# SlimPow-CB-v2.net
KiCad netlist of a schematic drawn in EAGLE
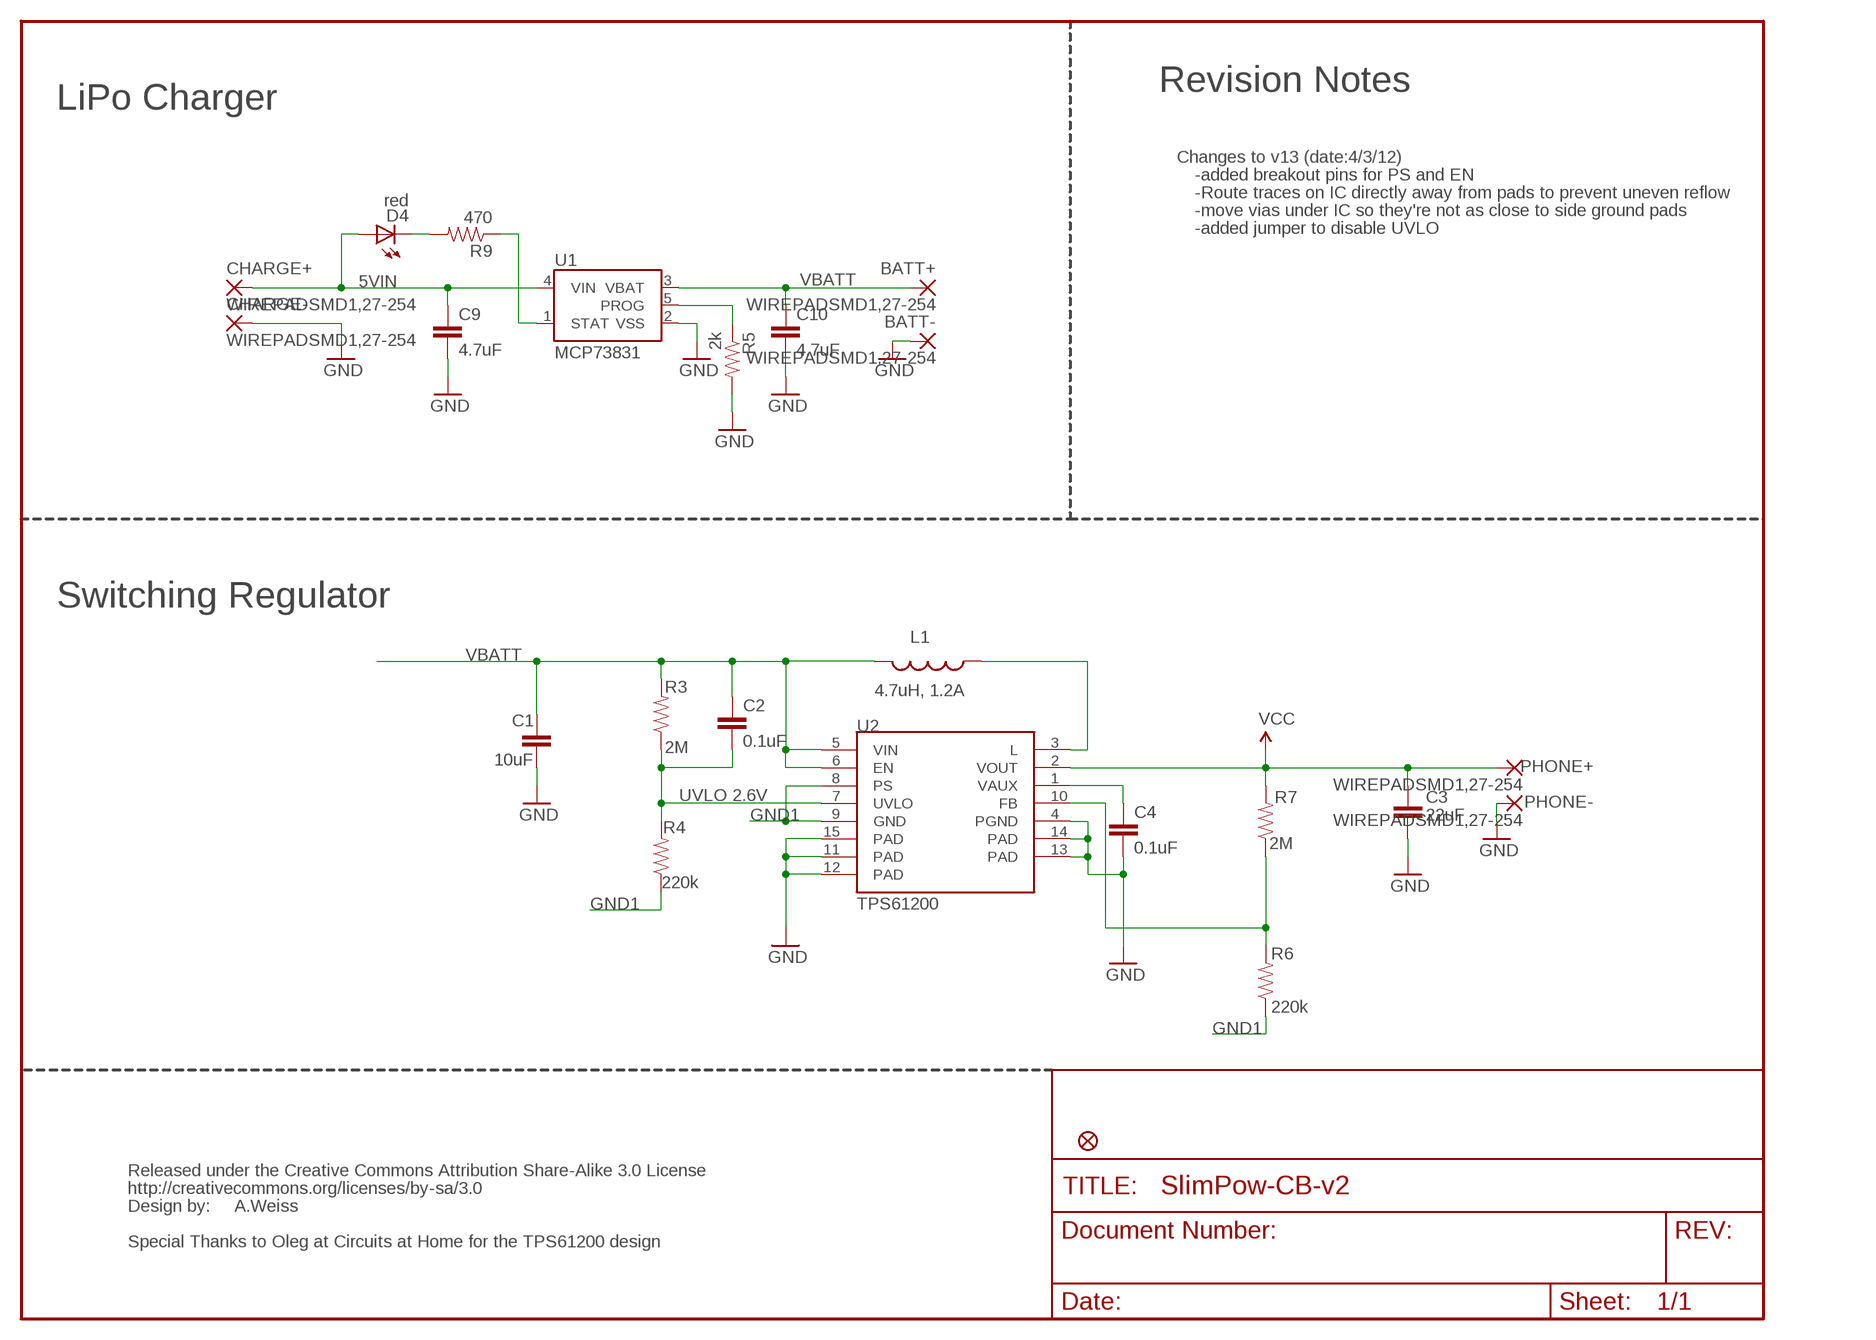
[diagram p0: schematic, sheet 1]

(export (version "E")
  (design (tool "Eeschema 10.0.6"))
  (components
    (comp (ref "BATT+")
      (value "WIREPADSMD1,27-254")
      (footprint "eagle-import:SMD1,27-2,54")
      (libsource (lib "eagle-import") (part "WIREPADSMD1,27-254"))
    )
    (comp (ref "BATT-")
      (value "WIREPADSMD1,27-254")
      (footprint "eagle-import:SMD1,27-2,54")
      (libsource (lib "eagle-import") (part "WIREPADSMD1,27-254"))
    )
    (comp (ref "C1")
      (value "10uF")
      (footprint "eagle-import:1206")
      (libsource (lib "eagle-import") (part "CAP1206"))
    )
    (comp (ref "C2")
      (value "0.1uF")
      (footprint "eagle-import:0402-CAP")
      (libsource (lib "eagle-import") (part "CAP0402-CAP"))
    )
    (comp (ref "C3")
      (value "22uF")
      (footprint "eagle-import:0805")
      (libsource (lib "eagle-import") (part "CAP0805"))
    )
    (comp (ref "C4")
      (value "0.1uF")
      (footprint "eagle-import:0402-CAP")
      (libsource (lib "eagle-import") (part "CAP0402-CAP"))
    )
    (comp (ref "C9")
      (value "4.7uF")
      (footprint "eagle-import:0402-CAP")
      (libsource (lib "eagle-import") (part "CAP0402-CAP"))
    )
    (comp (ref "C10")
      (value "4.7uF")
      (footprint "eagle-import:0402-CAP")
      (libsource (lib "eagle-import") (part "CAP0402-CAP"))
    )
    (comp (ref "CHARGE+")
      (value "WIREPADSMD1,27-254")
      (footprint "eagle-import:SMD1,27-2,54")
      (libsource (lib "eagle-import") (part "WIREPADSMD1,27-254"))
    )
    (comp (ref "CHARGE-")
      (value "WIREPADSMD1,27-254")
      (footprint "eagle-import:SMD1,27-2,54")
      (libsource (lib "eagle-import") (part "WIREPADSMD1,27-254"))
    )
    (comp (ref "D4")
      (value "red")
      (footprint "eagle-import:LED-0603")
      (libsource (lib "eagle-import") (part "LED0603"))
    )
    (comp (ref "JP15")
      (value "FIDUCIALUFIDUCIAL")
      (footprint "eagle-import:MICRO-FIDUCIAL")
      (libsource (lib "eagle-import") (part "FIDUCIALUFIDUCIAL"))
    )
    (comp (ref "L1")
      (value "4.7uH, 1.2A")
      (footprint "eagle-import:CDRH2D09")
      (libsource (lib "eagle-import") (part "INDUCTOR."))
    )
    (comp (ref "PHONE+")
      (value "WIREPADSMD1,27-254")
      (footprint "eagle-import:SMD1,27-2,54")
      (libsource (lib "eagle-import") (part "WIREPADSMD1,27-254"))
    )
    (comp (ref "PHONE-")
      (value "WIREPADSMD1,27-254")
      (footprint "eagle-import:SMD1,27-2,54")
      (libsource (lib "eagle-import") (part "WIREPADSMD1,27-254"))
    )
    (comp (ref "R3")
      (value "2M")
      (footprint "eagle-import:0402-RES")
      (libsource (lib "eagle-import") (part "RESISTOR0402-RES"))
    )
    (comp (ref "R4")
      (value "220k")
      (footprint "eagle-import:0402-RES")
      (libsource (lib "eagle-import") (part "RESISTOR0402-RES"))
    )
    (comp (ref "R5")
      (value "2k")
      (footprint "eagle-import:0402-RES")
      (libsource (lib "eagle-import") (part "RESISTOR0402-RES"))
    )
    (comp (ref "R6")
      (value "220k")
      (footprint "eagle-import:0402-RES")
      (libsource (lib "eagle-import") (part "RESISTOR0402-RES"))
    )
    (comp (ref "R7")
      (value "2M")
      (footprint "eagle-import:0402-RES")
      (libsource (lib "eagle-import") (part "RESISTOR0402-RES"))
    )
    (comp (ref "R9")
      (value "470")
      (footprint "eagle-import:0402-RES")
      (libsource (lib "eagle-import") (part "RESISTOR0402-RES"))
    )
    (comp (ref "U$2")
      (value "CREATIVE_COMMONS")
      (footprint "eagle-import:CREATIVE_COMMONS")
      (libsource (lib "eagle-import") (part "CREATIVE_COMMONS"))
    )
    (comp (ref "U1")
      (value "MCP73831")
      (footprint "eagle-import:SOT23-5")
      (libsource (lib "eagle-import") (part "MCP73831"))
    )
    (comp (ref "U2")
      (value "TPS61200")
      (footprint "eagle-import:QFN-10_PAD")
      (libsource (lib "eagle-import") (part "TPS61200"))
    )
  )
  (nets
    (net (code "1") (name "/5VIN") (class "Default")
      (node (ref "C9") (pin "1") (pinfunction "1_1") (pintype "passive"))
      (node (ref "CHARGE+") (pin "1") (pinfunction "P_1") (pintype "passive"))
      (node (ref "D4") (pin "A") (pinfunction "A_A") (pintype "passive"))
      (node (ref "U1") (pin "4") (pinfunction "VIN_4") (pintype "power_in"))
    )
    (net (code "2") (name "/GND1") (class "Default")
      (node (ref "R4") (pin "1") (pinfunction "1_1") (pintype "passive"))
      (node (ref "R6") (pin "1") (pinfunction "1_1") (pintype "passive"))
      (node (ref "U2") (pin "8") (pinfunction "PS_8") (pintype "input"))
      (node (ref "U2") (pin "9") (pinfunction "GND_9") (pintype "power_in"))
    )
    (net (code "3") (name "/VBATT") (class "Default")
      (node (ref "BATT+") (pin "1") (pinfunction "P_1") (pintype "passive"))
      (node (ref "C1") (pin "1") (pinfunction "1_1") (pintype "passive"))
      (node (ref "C10") (pin "1") (pinfunction "1_1") (pintype "passive"))
      (node (ref "C2") (pin "1") (pinfunction "1_1") (pintype "passive"))
      (node (ref "L1") (pin "P$2") (pinfunction "2_P$2") (pintype "passive"))
      (node (ref "R3") (pin "2") (pinfunction "2_2") (pintype "passive"))
      (node (ref "U1") (pin "3") (pinfunction "VBAT_3") (pintype "power_in"))
      (node (ref "U2") (pin "5") (pinfunction "VIN_5") (pintype "power_in"))
      (node (ref "U2") (pin "6") (pinfunction "EN_6") (pintype "input"))
    )
    (net (code "4") (name "GND") (class "Default")
      (node (ref "BATT-") (pin "1") (pinfunction "P_1") (pintype "passive"))
      (node (ref "C1") (pin "2") (pinfunction "2_2") (pintype "passive"))
      (node (ref "C10") (pin "2") (pinfunction "2_2") (pintype "passive"))
      (node (ref "C3") (pin "2") (pinfunction "2_2") (pintype "passive"))
      (node (ref "C4") (pin "2") (pinfunction "2_2") (pintype "passive"))
      (node (ref "C9") (pin "2") (pinfunction "2_2") (pintype "passive"))
      (node (ref "CHARGE-") (pin "1") (pinfunction "P_1") (pintype "passive"))
      (node (ref "PHONE-") (pin "1") (pinfunction "P_1") (pintype "passive"))
      (node (ref "R5") (pin "2") (pinfunction "2_2") (pintype "passive"))
      (node (ref "U1") (pin "2") (pinfunction "VSS_2") (pintype "power_in"))
      (node (ref "U2") (pin "11") (pinfunction "PAD_11") (pintype "power_in"))
      (node (ref "U2") (pin "12") (pinfunction "PAD_12") (pintype "power_in"))
      (node (ref "U2") (pin "13") (pinfunction "PAD_13") (pintype "power_in"))
      (node (ref "U2") (pin "14") (pinfunction "PAD_14") (pintype "power_in"))
      (node (ref "U2") (pin "15") (pinfunction "PAD_15") (pintype "power_in"))
      (node (ref "U2") (pin "4") (pinfunction "PGND_4") (pintype "power_in"))
    )
    (net (code "5") (name "Net-(D4-PadC)") (class "Default")
      (node (ref "D4") (pin "C") (pinfunction "C_C") (pintype "passive"))
      (node (ref "R9") (pin "2") (pinfunction "2_2") (pintype "passive"))
    )
    (net (code "6") (name "Net-(L1-1)") (class "Default")
      (node (ref "L1") (pin "P$1") (pinfunction "1_P$1") (pintype "passive"))
      (node (ref "U2") (pin "3") (pinfunction "L_3") (pintype "passive"))
    )
    (net (code "7") (name "Net-(U1-PROG)") (class "Default")
      (node (ref "R5") (pin "1") (pinfunction "1_1") (pintype "passive"))
      (node (ref "U1") (pin "5") (pinfunction "PROG_5") (pintype "input"))
    )
    (net (code "8") (name "Net-(U1-STAT)") (class "Default")
      (node (ref "R9") (pin "1") (pinfunction "1_1") (pintype "passive"))
      (node (ref "U1") (pin "1") (pinfunction "STAT_1") (pintype "output"))
    )
    (net (code "9") (name "Net-(U2-FB)") (class "Default")
      (node (ref "R6") (pin "2") (pinfunction "2_2") (pintype "passive"))
      (node (ref "R7") (pin "1") (pinfunction "1_1") (pintype "passive"))
      (node (ref "U2") (pin "10") (pinfunction "FB_10") (pintype "passive"))
    )
    (net (code "10") (name "Net-(U2-UVLO)") (class "Default")
      (node (ref "C2") (pin "2") (pinfunction "2_2") (pintype "passive"))
      (node (ref "R3") (pin "1") (pinfunction "1_1") (pintype "passive"))
      (node (ref "R4") (pin "2") (pinfunction "2_2") (pintype "passive"))
      (node (ref "U2") (pin "7") (pinfunction "UVLO_7") (pintype "passive"))
    )
    (net (code "11") (name "Net-(U2-VAUX)") (class "Default")
      (node (ref "C4") (pin "1") (pinfunction "1_1") (pintype "passive"))
      (node (ref "U2") (pin "1") (pinfunction "VAUX_1") (pintype "passive"))
    )
    (net (code "12") (name "VCC") (class "Default")
      (node (ref "C3") (pin "1") (pinfunction "1_1") (pintype "passive"))
      (node (ref "PHONE+") (pin "1") (pinfunction "P_1") (pintype "passive"))
      (node (ref "R7") (pin "2") (pinfunction "2_2") (pintype "passive"))
      (node (ref "U2") (pin "2") (pinfunction "VOUT_2") (pintype "passive"))
    )
  )
)
